# Camara_V4_LOCK.net
KiCad netlist of a schematic drawn in EAGLE
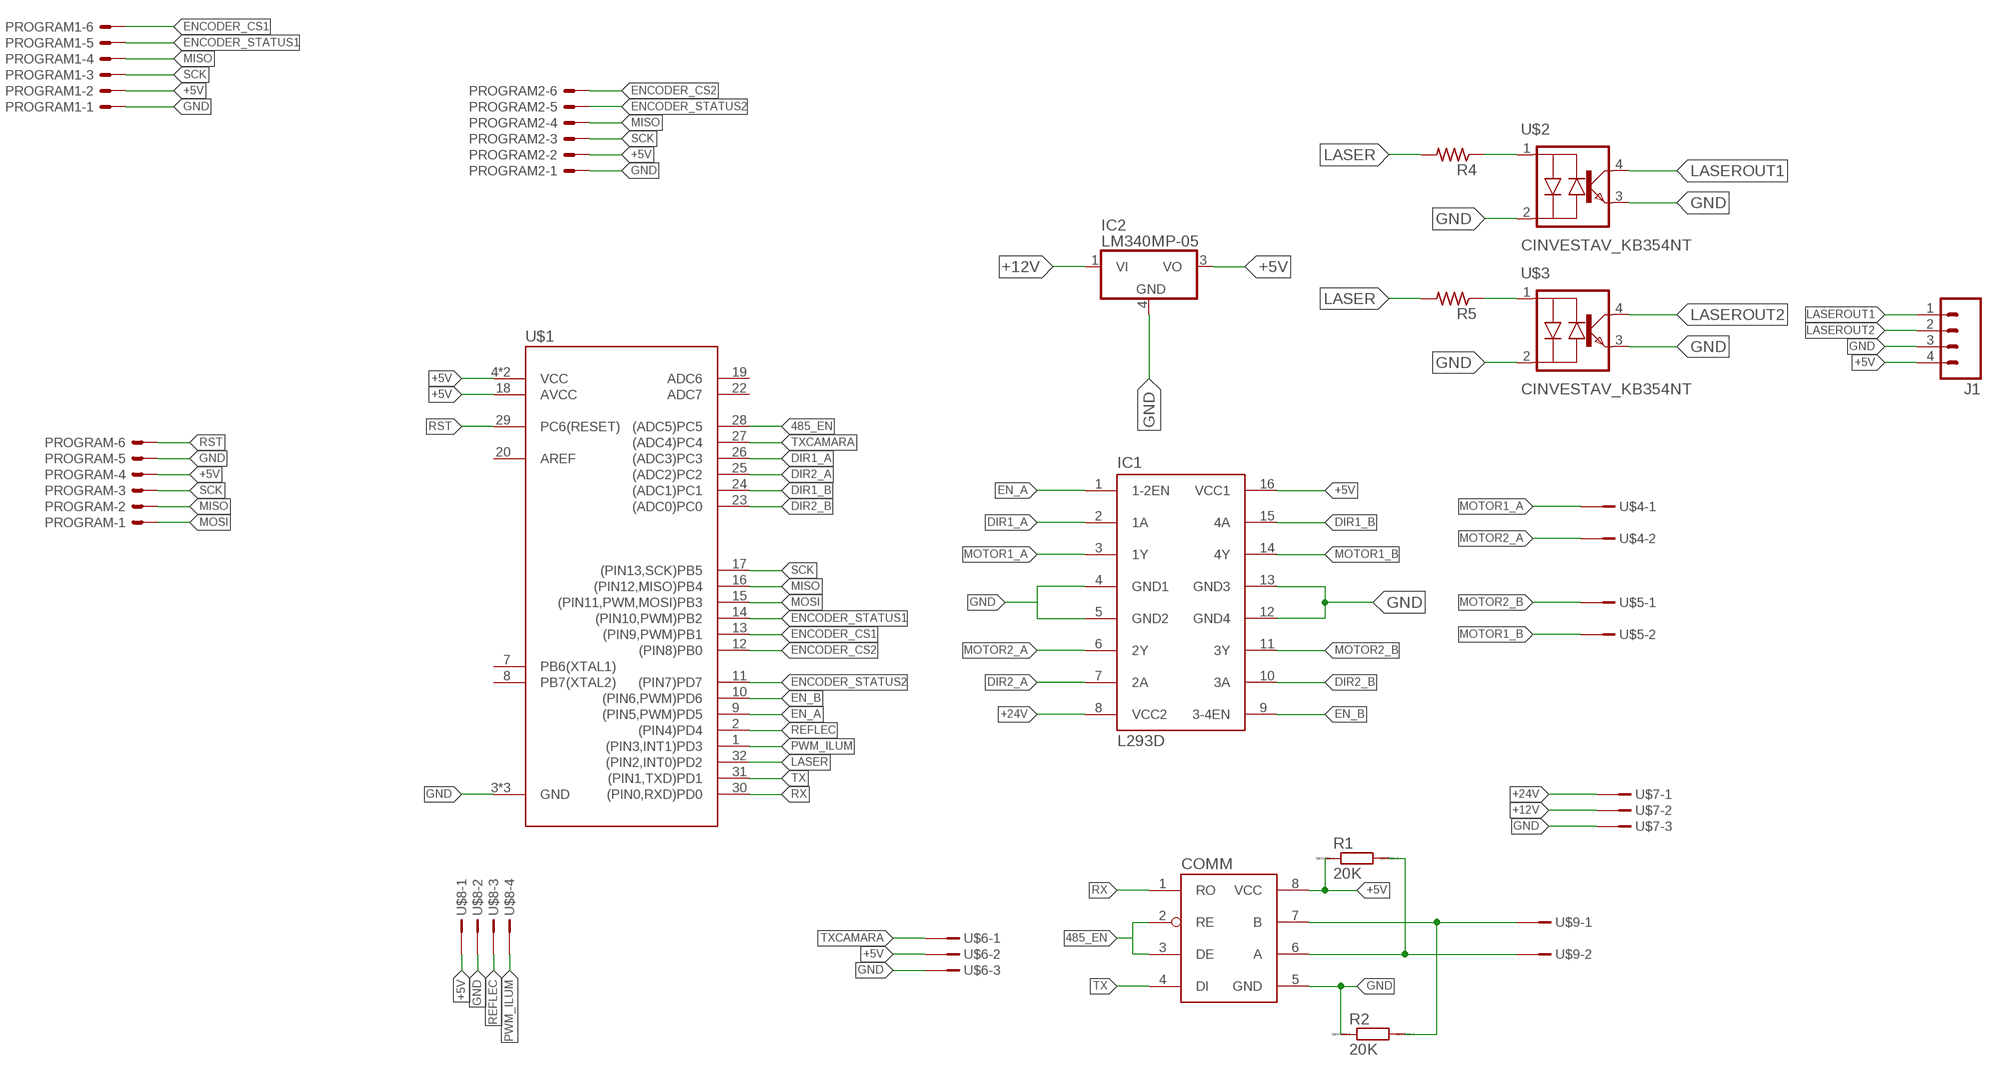
[diagram p0: schematic, sheet 1]

(export (version "E")
  (design (tool "Eeschema 10.0.6"))
  (components
    (comp (ref "COMM")
      (value "CINVESTAV_ADM1485")
      (footprint "eagle-import:CINVESTAV_SOIC8")
      (libsource (lib "eagle-import") (part "CINVESTAV_ADM1485"))
    )
    (comp (ref "IC1")
      (value "L293D")
      (footprint "eagle-import:DIL16")
      (libsource (lib "eagle-import") (part "L293D"))
    )
    (comp (ref "IC2")
      (value "LM340MP-05")
      (footprint "eagle-import:SOT223")
      (libsource (lib "eagle-import") (part "LM340?-MP05"))
    )
    (comp (ref "J1")
      (value "M04JST-PTH-VERT")
      (footprint "eagle-import:JST-4-PTH-VERT")
      (libsource (lib "eagle-import") (part "M04JST-PTH-VERT"))
    )
    (comp (ref "PROGRAM")
      (value "22-23-2061")
      (footprint "eagle-import:22-23-2061")
      (fields (field (name "MF") "MOLEX"))
      (libsource (lib "eagle-import") (part "22-23-2061"))
    )
    (comp (ref "PROGRAM1")
      (value "22-23-2061")
      (footprint "eagle-import:22-23-2061")
      (fields (field (name "MF") "MOLEX"))
      (libsource (lib "eagle-import") (part "22-23-2061"))
    )
    (comp (ref "PROGRAM2")
      (value "22-23-2061")
      (footprint "eagle-import:22-23-2061")
      (fields (field (name "MF") "MOLEX"))
      (libsource (lib "eagle-import") (part "22-23-2061"))
    )
    (comp (ref "R1")
      (value "20K")
      (footprint "eagle-import:R1206")
      (libsource (lib "eagle-import") (part "RR1206"))
    )
    (comp (ref "R2")
      (value "20K")
      (footprint "eagle-import:R1206")
      (libsource (lib "eagle-import") (part "RR1206"))
    )
    (comp (ref "R4")
      (value "R-US_M1206")
      (footprint "eagle-import:M1206")
      (libsource (lib "eagle-import") (part "R-US_M1206"))
    )
    (comp (ref "R5")
      (value "R-US_M1206")
      (footprint "eagle-import:M1206")
      (libsource (lib "eagle-import") (part "R-US_M1206"))
    )
    (comp (ref "U$1")
      (value "CINVESTAV_ATMEGA328")
      (footprint "eagle-import:CINVESTAV_TQFP32-08")
      (libsource (lib "eagle-import") (part "CINVESTAV_ATMEGA328"))
    )
    (comp (ref "U$2")
      (value "CINVESTAV_KB354NT")
      (footprint "eagle-import:CINVESTAV_SOIC4")
      (libsource (lib "eagle-import") (part "CINVESTAV_KB354NT"))
    )
    (comp (ref "U$3")
      (value "CINVESTAV_KB354NT")
      (footprint "eagle-import:CINVESTAV_SOIC4")
      (libsource (lib "eagle-import") (part "CINVESTAV_KB354NT"))
    )
    (comp (ref "U$4")
      (value "XH-02")
      (footprint "eagle-import:XH-02")
      (libsource (lib "eagle-import") (part "XH-02"))
    )
    (comp (ref "U$5")
      (value "XH-02")
      (footprint "eagle-import:XH-02")
      (libsource (lib "eagle-import") (part "XH-02"))
    )
    (comp (ref "U$6")
      (value "XH-03")
      (footprint "eagle-import:XH-03")
      (libsource (lib "eagle-import") (part "XH-03"))
    )
    (comp (ref "U$7")
      (value "XH-03")
      (footprint "eagle-import:XH-03")
      (libsource (lib "eagle-import") (part "XH-03"))
    )
    (comp (ref "U$8")
      (value "XH-04")
      (footprint "eagle-import:XH-04")
      (libsource (lib "eagle-import") (part "XH-04"))
    )
    (comp (ref "U$9")
      (value "XH-02")
      (footprint "eagle-import:XH-02")
      (libsource (lib "eagle-import") (part "XH-02"))
    )
  )
  (nets
    (net (code "1") (name "+5V") (class "Default")
      (node (ref "COMM") (pin "8") (pinfunction "VCC_8") (pintype "power_in"))
      (node (ref "IC1") (pin "16") (pinfunction "VCC1_16") (pintype "power_in"))
      (node (ref "IC2") (pin "3") (pinfunction "VO_3") (pintype "passive"))
      (node (ref "J1") (pin "4") (pinfunction "4_4") (pintype "passive"))
      (node (ref "PROGRAM") (pin "4") (pinfunction "S_4") (pintype "passive"))
      (node (ref "PROGRAM1") (pin "2") (pinfunction "S_2") (pintype "passive"))
      (node (ref "PROGRAM2") (pin "2") (pinfunction "S_2") (pintype "passive"))
      (node (ref "R1") (pin "1") (pinfunction "1_1") (pintype "passive"))
      (node (ref "U$1") (pin "18") (pinfunction "AVCC_18") (pintype "power_in"))
      (node (ref "U$1") (pin "4") (pinfunction "VCC_4") (pintype "power_in"))
      (node (ref "U$1") (pin "6") (pinfunction "VCC_6") (pintype "power_in"))
      (node (ref "U$6") (pin "P$2") (pinfunction "1_P$2") (pintype "passive"))
      (node (ref "U$8") (pin "P$1") (pinfunction "1_P$1") (pintype "passive"))
    )
    (net (code "2") (name "+12V") (class "Default")
      (node (ref "IC2") (pin "1") (pinfunction "VI_1") (pintype "input"))
      (node (ref "U$7") (pin "P$2") (pinfunction "1_P$2") (pintype "passive"))
    )
    (net (code "3") (name "+24V") (class "Default")
      (node (ref "IC1") (pin "8") (pinfunction "VCC2_8") (pintype "power_in"))
      (node (ref "U$7") (pin "P$1") (pinfunction "1_P$1") (pintype "passive"))
    )
    (net (code "4") (name "485_EN") (class "Default")
      (node (ref "COMM") (pin "2") (pinfunction "RE_2") (pintype "input"))
      (node (ref "COMM") (pin "3") (pinfunction "DE_3") (pintype "input"))
      (node (ref "U$1") (pin "28") (pinfunction "(ADC5)PC5_28") (pintype "bidirectional"))
    )
    (net (code "5") (name "DIR1_A") (class "Default")
      (node (ref "IC1") (pin "2") (pinfunction "1A_2") (pintype "input"))
      (node (ref "U$1") (pin "26") (pinfunction "(ADC3)PC3_26") (pintype "bidirectional"))
    )
    (net (code "6") (name "DIR1_B") (class "Default")
      (node (ref "IC1") (pin "15") (pinfunction "4A_15") (pintype "input"))
      (node (ref "U$1") (pin "24") (pinfunction "(ADC1)PC1_24") (pintype "bidirectional"))
    )
    (net (code "7") (name "DIR2_A") (class "Default")
      (node (ref "IC1") (pin "7") (pinfunction "2A_7") (pintype "input"))
      (node (ref "U$1") (pin "25") (pinfunction "(ADC2)PC2_25") (pintype "bidirectional"))
    )
    (net (code "8") (name "DIR2_B") (class "Default")
      (node (ref "IC1") (pin "10") (pinfunction "3A_10") (pintype "input"))
      (node (ref "U$1") (pin "23") (pinfunction "(ADC0)PC0_23") (pintype "bidirectional"))
    )
    (net (code "9") (name "ENCODER_CS1") (class "Default")
      (node (ref "PROGRAM1") (pin "6") (pinfunction "S_6") (pintype "passive"))
      (node (ref "U$1") (pin "13") (pinfunction "(PIN9,PWM)PB1_13") (pintype "bidirectional"))
    )
    (net (code "10") (name "ENCODER_CS2") (class "Default")
      (node (ref "PROGRAM2") (pin "6") (pinfunction "S_6") (pintype "passive"))
      (node (ref "U$1") (pin "12") (pinfunction "(PIN8)PB0_12") (pintype "bidirectional"))
    )
    (net (code "11") (name "ENCODER_STATUS1") (class "Default")
      (node (ref "PROGRAM1") (pin "5") (pinfunction "S_5") (pintype "passive"))
      (node (ref "U$1") (pin "14") (pinfunction "(PIN10,PWM)PB2_14") (pintype "bidirectional"))
    )
    (net (code "12") (name "ENCODER_STATUS2") (class "Default")
      (node (ref "PROGRAM2") (pin "5") (pinfunction "S_5") (pintype "passive"))
      (node (ref "U$1") (pin "11") (pinfunction "(PIN7)PD7_11") (pintype "bidirectional"))
    )
    (net (code "13") (name "EN_A") (class "Default")
      (node (ref "IC1") (pin "1") (pinfunction "1-2EN_1") (pintype "input"))
      (node (ref "U$1") (pin "9") (pinfunction "(PIN5,PWM)PD5_9") (pintype "bidirectional"))
    )
    (net (code "14") (name "EN_B") (class "Default")
      (node (ref "IC1") (pin "9") (pinfunction "3-4EN_9") (pintype "input"))
      (node (ref "U$1") (pin "10") (pinfunction "(PIN6,PWM)PD6_10") (pintype "bidirectional"))
    )
    (net (code "15") (name "GND") (class "Default")
      (node (ref "COMM") (pin "5") (pinfunction "GND_5") (pintype "power_in"))
      (node (ref "IC1") (pin "12") (pinfunction "GND4_12") (pintype "power_in"))
      (node (ref "IC1") (pin "13") (pinfunction "GND3_13") (pintype "power_in"))
      (node (ref "IC1") (pin "4") (pinfunction "GND1_4") (pintype "power_in"))
      (node (ref "IC1") (pin "5") (pinfunction "GND2_5") (pintype "power_in"))
      (node (ref "IC2") (pin "4") (pinfunction "GND_4") (pintype "passive"))
      (node (ref "J1") (pin "3") (pinfunction "3_3") (pintype "passive"))
      (node (ref "PROGRAM") (pin "5") (pinfunction "S_5") (pintype "passive"))
      (node (ref "PROGRAM1") (pin "1") (pinfunction "S_1") (pintype "passive"))
      (node (ref "PROGRAM2") (pin "1") (pinfunction "S_1") (pintype "passive"))
      (node (ref "R2") (pin "1") (pinfunction "1_1") (pintype "passive"))
      (node (ref "U$1") (pin "21") (pinfunction "GND_21") (pintype "power_in"))
      (node (ref "U$1") (pin "3") (pinfunction "GND_3") (pintype "power_in"))
      (node (ref "U$1") (pin "5") (pinfunction "GND_5") (pintype "power_in"))
      (node (ref "U$2") (pin "2") (pinfunction "C/A_2") (pintype "bidirectional"))
      (node (ref "U$2") (pin "3") (pinfunction "EMIT_3") (pintype "bidirectional"))
      (node (ref "U$3") (pin "2") (pinfunction "C/A_2") (pintype "bidirectional"))
      (node (ref "U$3") (pin "3") (pinfunction "EMIT_3") (pintype "bidirectional"))
      (node (ref "U$6") (pin "P$3") (pinfunction "1_P$3") (pintype "passive"))
      (node (ref "U$7") (pin "P$3") (pinfunction "1_P$3") (pintype "passive"))
      (node (ref "U$8") (pin "P$2") (pinfunction "1_P$2") (pintype "passive"))
    )
    (net (code "16") (name "LASER") (class "Default")
      (node (ref "R4") (pin "2") (pinfunction "2_2") (pintype "passive"))
      (node (ref "R5") (pin "2") (pinfunction "2_2") (pintype "passive"))
      (node (ref "U$1") (pin "32") (pinfunction "(PIN2,INT0)PD2_32") (pintype "bidirectional"))
    )
    (net (code "17") (name "LASEROUT1") (class "Default")
      (node (ref "J1") (pin "1") (pinfunction "1_1") (pintype "passive"))
      (node (ref "U$2") (pin "4") (pinfunction "COL_4") (pintype "bidirectional"))
    )
    (net (code "18") (name "LASEROUT2") (class "Default")
      (node (ref "J1") (pin "2") (pinfunction "2_2") (pintype "passive"))
      (node (ref "U$3") (pin "4") (pinfunction "COL_4") (pintype "bidirectional"))
    )
    (net (code "19") (name "MISO") (class "Default")
      (node (ref "PROGRAM") (pin "2") (pinfunction "S_2") (pintype "passive"))
      (node (ref "PROGRAM1") (pin "4") (pinfunction "S_4") (pintype "passive"))
      (node (ref "PROGRAM2") (pin "4") (pinfunction "S_4") (pintype "passive"))
      (node (ref "U$1") (pin "16") (pinfunction "(PIN12,MISO)PB4_16") (pintype "bidirectional"))
    )
    (net (code "20") (name "MOSI") (class "Default")
      (node (ref "PROGRAM") (pin "1") (pinfunction "S_1") (pintype "passive"))
      (node (ref "U$1") (pin "15") (pinfunction "(PIN11,PWM,MOSI)PB3_15") (pintype "bidirectional"))
    )
    (net (code "21") (name "MOTOR1_A") (class "Default")
      (node (ref "IC1") (pin "3") (pinfunction "1Y_3") (pintype "output"))
      (node (ref "U$4") (pin "P$1") (pinfunction "1_P$1") (pintype "passive"))
    )
    (net (code "22") (name "MOTOR1_B") (class "Default")
      (node (ref "IC1") (pin "14") (pinfunction "4Y_14") (pintype "output"))
      (node (ref "U$5") (pin "P$2") (pinfunction "1_P$2") (pintype "passive"))
    )
    (net (code "23") (name "MOTOR2_A") (class "Default")
      (node (ref "IC1") (pin "6") (pinfunction "2Y_6") (pintype "output"))
      (node (ref "U$4") (pin "P$2") (pinfunction "1_P$2") (pintype "passive"))
    )
    (net (code "24") (name "MOTOR2_B") (class "Default")
      (node (ref "IC1") (pin "11") (pinfunction "3Y_11") (pintype "output"))
      (node (ref "U$5") (pin "P$1") (pinfunction "1_P$1") (pintype "passive"))
    )
    (net (code "25") (name "Net-(COMM-A)") (class "Default")
      (node (ref "COMM") (pin "6") (pinfunction "A_6") (pintype "bidirectional"))
      (node (ref "R1") (pin "2") (pinfunction "2_2") (pintype "passive"))
      (node (ref "U$9") (pin "P$2") (pinfunction "1_P$2") (pintype "passive"))
    )
    (net (code "26") (name "Net-(COMM-B)") (class "Default")
      (node (ref "COMM") (pin "7") (pinfunction "B_7") (pintype "bidirectional"))
      (node (ref "R2") (pin "2") (pinfunction "2_2") (pintype "passive"))
      (node (ref "U$9") (pin "P$1") (pinfunction "1_P$1") (pintype "passive"))
    )
    (net (code "27") (name "Net-(U$2-A{slash}C)") (class "Default")
      (node (ref "R4") (pin "1") (pinfunction "1_1") (pintype "passive"))
      (node (ref "U$2") (pin "1") (pinfunction "A/C_1") (pintype "bidirectional"))
    )
    (net (code "28") (name "Net-(U$3-A{slash}C)") (class "Default")
      (node (ref "R5") (pin "1") (pinfunction "1_1") (pintype "passive"))
      (node (ref "U$3") (pin "1") (pinfunction "A/C_1") (pintype "bidirectional"))
    )
    (net (code "29") (name "PWM_ILUM") (class "Default")
      (node (ref "U$1") (pin "1") (pinfunction "(PIN3,INT1)PD3_1") (pintype "bidirectional"))
      (node (ref "U$8") (pin "P$4") (pinfunction "1_P$4") (pintype "passive"))
    )
    (net (code "30") (name "REFLEC") (class "Default")
      (node (ref "U$1") (pin "2") (pinfunction "(PIN4)PD4_2") (pintype "bidirectional"))
      (node (ref "U$8") (pin "P$3") (pinfunction "1_P$3") (pintype "passive"))
    )
    (net (code "31") (name "RST") (class "Default")
      (node (ref "PROGRAM") (pin "6") (pinfunction "S_6") (pintype "passive"))
      (node (ref "U$1") (pin "29") (pinfunction "PC6(RESET)_29") (pintype "bidirectional"))
    )
    (net (code "32") (name "RX") (class "Default")
      (node (ref "COMM") (pin "1") (pinfunction "RO_1") (pintype "output"))
      (node (ref "U$1") (pin "30") (pinfunction "(PIN0,RXD)PD0_30") (pintype "bidirectional"))
    )
    (net (code "33") (name "SCK") (class "Default")
      (node (ref "PROGRAM") (pin "3") (pinfunction "S_3") (pintype "passive"))
      (node (ref "PROGRAM1") (pin "3") (pinfunction "S_3") (pintype "passive"))
      (node (ref "PROGRAM2") (pin "3") (pinfunction "S_3") (pintype "passive"))
      (node (ref "U$1") (pin "17") (pinfunction "(PIN13,SCK)PB5_17") (pintype "bidirectional"))
    )
    (net (code "34") (name "TX") (class "Default")
      (node (ref "COMM") (pin "4") (pinfunction "DI_4") (pintype "input"))
      (node (ref "U$1") (pin "31") (pinfunction "(PIN1,TXD)PD1_31") (pintype "bidirectional"))
    )
    (net (code "35") (name "TXCAMARA") (class "Default")
      (node (ref "U$1") (pin "27") (pinfunction "(ADC4)PC4_27") (pintype "bidirectional"))
      (node (ref "U$6") (pin "P$1") (pinfunction "1_P$1") (pintype "passive"))
    )
    (net (code "36") (name "unconnected-(U$1-ADC6-Pad19)") (class "Default")
      (node (ref "U$1") (pin "19") (pinfunction "ADC6_19") (pintype "bidirectional"))
    )
    (net (code "37") (name "unconnected-(U$1-ADC7-Pad22)") (class "Default")
      (node (ref "U$1") (pin "22") (pinfunction "ADC7_22") (pintype "bidirectional"))
    )
    (net (code "38") (name "unconnected-(U$1-AREF-Pad20)") (class "Default")
      (node (ref "U$1") (pin "20") (pinfunction "AREF_20") (pintype "passive"))
    )
    (net (code "39") (name "unconnected-(U$1-PB6(XTAL1)-Pad7)") (class "Default")
      (node (ref "U$1") (pin "7") (pinfunction "PB6(XTAL1)_7") (pintype "bidirectional"))
    )
    (net (code "40") (name "unconnected-(U$1-PB7(XTAL2)-Pad8)") (class "Default")
      (node (ref "U$1") (pin "8") (pinfunction "PB7(XTAL2)_8") (pintype "bidirectional"))
    )
  )
)
